# VisualightMicroBulb_04.net
KiCad netlist of a schematic drawn in EAGLE
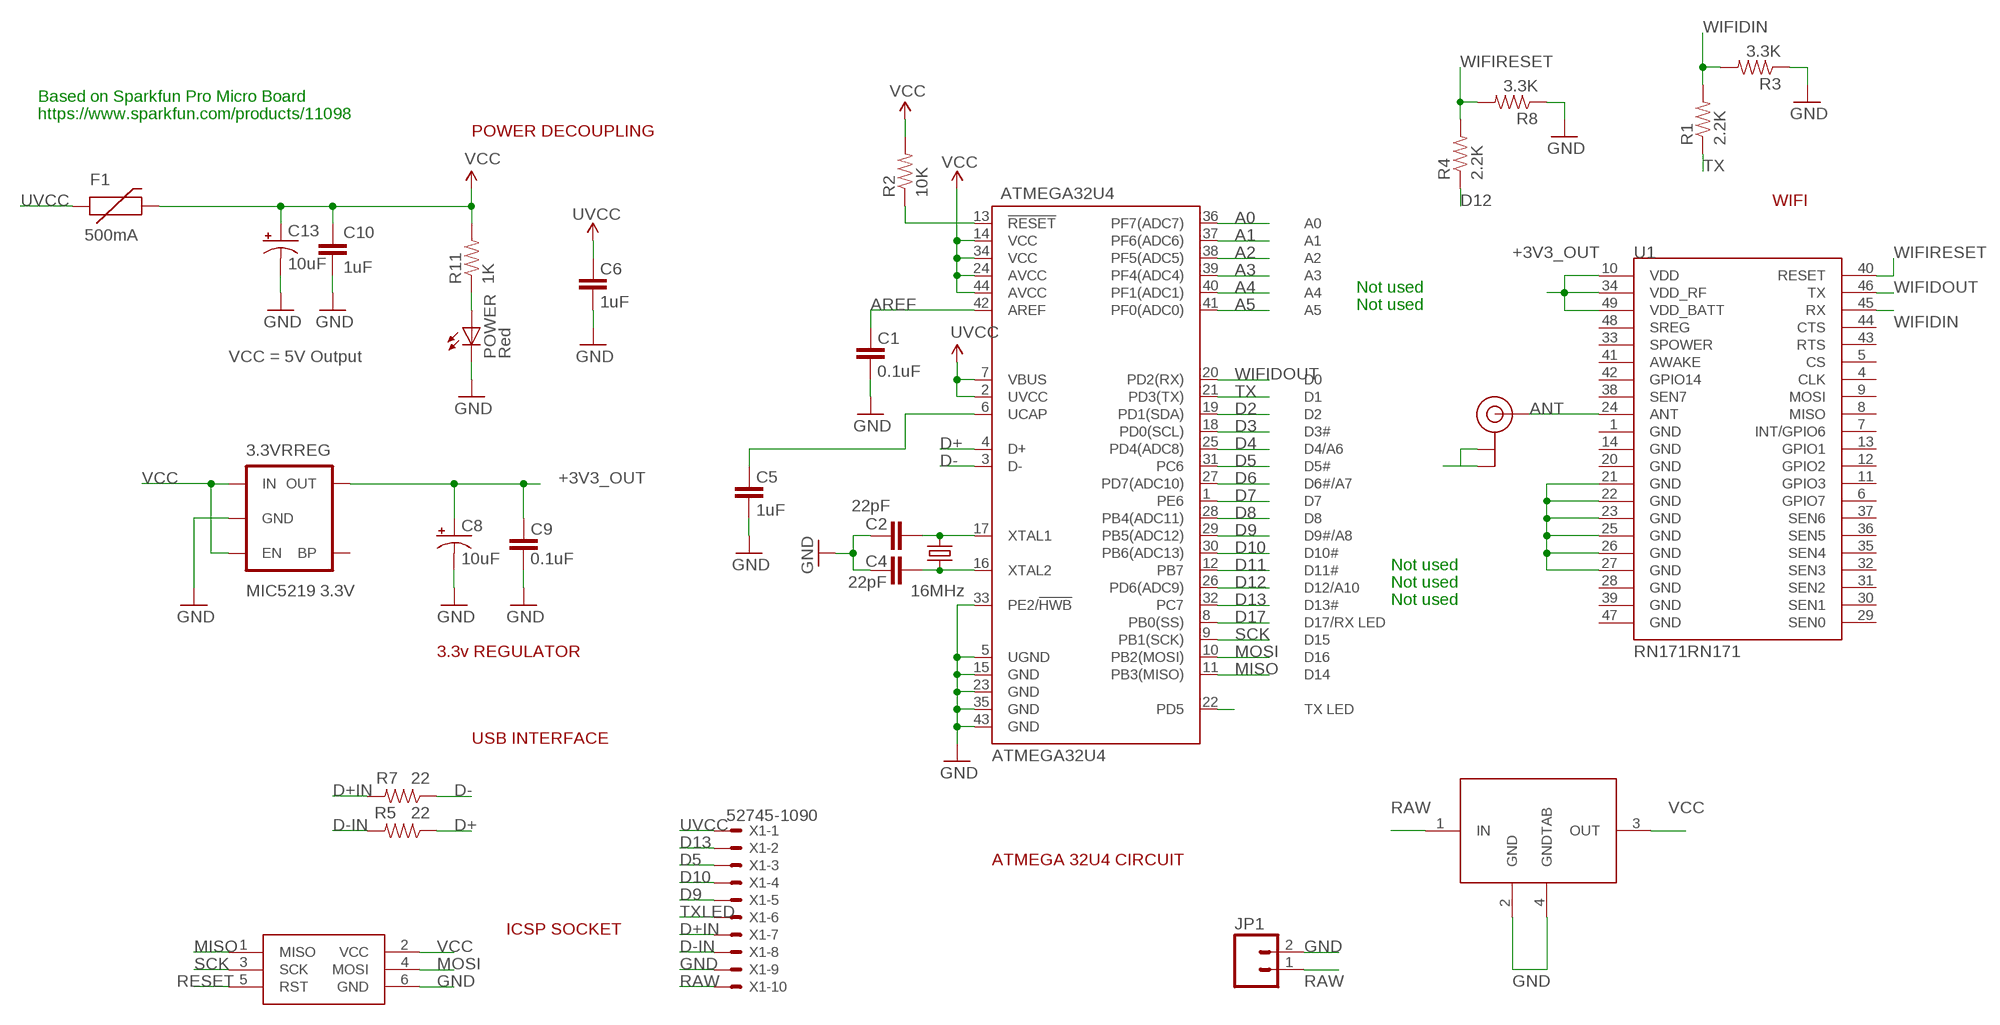
[diagram p0: schematic, sheet 1]

(export (version "E")
  (design (tool "Eeschema 10.0.6"))
  (components
    (comp (ref "3.3VRREG")
      (value "MIC5219 3.3V")
      (footprint "eagle-import:SOT23-5")
      (libsource (lib "eagle-import") (part "V_REG_MIC52193.3V"))
    )
    (comp (ref "ATMEGA32U4")
      (value "ATMEGA32U4")
      (footprint "eagle-import:SPARKFUN-DIGITALIC_TQFP44")
      (libsource (lib "eagle-import") (part "ATMEGA32U4TQFP"))
    )
    (comp (ref "C1")
      (value "0.1uF")
      (footprint "eagle-import:0402-CAP")
      (libsource (lib "eagle-import") (part "CAP0402-CAP"))
    )
    (comp (ref "C2")
      (value "22pF")
      (footprint "eagle-import:0402-CAP")
      (libsource (lib "eagle-import") (part "CAP0402-CAP"))
    )
    (comp (ref "C4")
      (value "22pF")
      (footprint "eagle-import:0402-CAP")
      (libsource (lib "eagle-import") (part "CAP0402-CAP"))
    )
    (comp (ref "C5")
      (value "1uF")
      (footprint "eagle-import:0402-CAP")
      (libsource (lib "eagle-import") (part "CAP0402-CAP"))
    )
    (comp (ref "C6")
      (value "1uF")
      (footprint "eagle-import:0402-CAP")
      (libsource (lib "eagle-import") (part "CAP0402-CAP"))
    )
    (comp (ref "C8")
      (value "10uF")
      (footprint "eagle-import:EIA3216")
      (libsource (lib "eagle-import") (part "CAP_POL1206"))
    )
    (comp (ref "C9")
      (value "0.1uF")
      (footprint "eagle-import:0402-CAP")
      (libsource (lib "eagle-import") (part "CAP0402-CAP"))
    )
    (comp (ref "C10")
      (value "1uF")
      (footprint "eagle-import:0402-CAP")
      (libsource (lib "eagle-import") (part "CAP0402-CAP"))
    )
    (comp (ref "C13")
      (value "10uF")
      (footprint "eagle-import:EIA3216")
      (libsource (lib "eagle-import") (part "CAP_POL1206"))
    )
    (comp (ref "F1")
      (value "500mA")
      (footprint "eagle-import:PTC-1206")
      (libsource (lib "eagle-import") (part "PTCSMD"))
    )
    (comp (ref "ISP1")
      (value "AVRISP-6")
      (footprint "eagle-import:AVRISP")
      (libsource (lib "eagle-import") (part "AVRISP-6"))
    )
    (comp (ref "JP1")
      (value "M02PTH")
      (footprint "eagle-import:1X02")
      (libsource (lib "eagle-import") (part "M02PTH"))
    )
    (comp (ref "POWER")
      (value "Red")
      (footprint "eagle-import:LED-0603")
      (libsource (lib "eagle-import") (part "LED0603"))
    )
    (comp (ref "R1")
      (value "2.2K")
      (footprint "eagle-import:0402-RES")
      (libsource (lib "eagle-import") (part "RESISTOR0402-RES"))
    )
    (comp (ref "R2")
      (value "10K")
      (footprint "eagle-import:0402-RES")
      (libsource (lib "eagle-import") (part "RESISTOR0402-RES"))
    )
    (comp (ref "R3")
      (value "3.3K")
      (footprint "eagle-import:0402-RES")
      (libsource (lib "eagle-import") (part "RESISTOR0402-RES"))
    )
    (comp (ref "R4")
      (value "2.2K")
      (footprint "eagle-import:0402-RES")
      (libsource (lib "eagle-import") (part "RESISTOR0402-RES"))
    )
    (comp (ref "R5")
      (value "22")
      (footprint "eagle-import:0402-RES")
      (libsource (lib "eagle-import") (part "RESISTOR0402-RES"))
    )
    (comp (ref "R7")
      (value "22")
      (footprint "eagle-import:0402-RES")
      (libsource (lib "eagle-import") (part "RESISTOR0402-RES"))
    )
    (comp (ref "R8")
      (value "3.3K")
      (footprint "eagle-import:0402-RES")
      (libsource (lib "eagle-import") (part "RESISTOR0402-RES"))
    )
    (comp (ref "R11")
      (value "1K")
      (footprint "eagle-import:0402-RES")
      (libsource (lib "eagle-import") (part "RESISTOR0402-RES"))
    )
    (comp (ref "U$1")
      (value "U.FL")
      (footprint "eagle-import:U.FL")
      (libsource (lib "eagle-import") (part "U.FL"))
    )
    (comp (ref "U$2")
      (value "MIC5239")
      (footprint "eagle-import:SOT223")
      (libsource (lib "eagle-import") (part "MIC5239"))
    )
    (comp (ref "U1")
      (value "RN171RN171")
      (footprint "eagle-import:RN171")
      (libsource (lib "eagle-import") (part "RN171RN171"))
    )
    (comp (ref "X1")
      (value "52745-1090")
      (footprint "eagle-import:52745-1090")
      (libsource (lib "eagle-import") (part "52745-1090"))
    )
    (comp (ref "Y1")
      (value "16MHz")
      (footprint "eagle-import:CRYSTAL-SMD-5X3")
      (libsource (lib "eagle-import") (part "CRYSTAL5X3"))
    )
  )
  (nets
    (net (code "1") (name "/+3V3_OUT") (class "Default")
      (node (ref "3.3VRREG") (pin "5") (pinfunction "OUT_5") (pintype "passive"))
      (node (ref "C8") (pin "A") (pinfunction "+_A") (pintype "passive"))
      (node (ref "C9") (pin "2") (pinfunction "2_2") (pintype "passive"))
      (node (ref "U1") (pin "10") (pinfunction "VDD_10") (pintype "bidirectional"))
      (node (ref "U1") (pin "34") (pinfunction "VDD_RF_34") (pintype "bidirectional"))
      (node (ref "U1") (pin "49") (pinfunction "VDD_BATT_49") (pintype "bidirectional"))
    )
    (net (code "2") (name "/A0") (class "Default")
      (node (ref "ATMEGA32U4") (pin "36") (pinfunction "PF7(ADC7)_36") (pintype "bidirectional"))
    )
    (net (code "3") (name "/A1") (class "Default")
      (node (ref "ATMEGA32U4") (pin "37") (pinfunction "PF6(ADC6)_37") (pintype "bidirectional"))
    )
    (net (code "4") (name "/A2") (class "Default")
      (node (ref "ATMEGA32U4") (pin "38") (pinfunction "PF5(ADC5)_38") (pintype "bidirectional"))
    )
    (net (code "5") (name "/A3") (class "Default")
      (node (ref "ATMEGA32U4") (pin "39") (pinfunction "PF4(ADC4)_39") (pintype "bidirectional"))
    )
    (net (code "6") (name "/A4") (class "Default")
      (node (ref "ATMEGA32U4") (pin "40") (pinfunction "PF1(ADC1)_40") (pintype "bidirectional"))
    )
    (net (code "7") (name "/A5") (class "Default")
      (node (ref "ATMEGA32U4") (pin "41") (pinfunction "PF0(ADC0)_41") (pintype "bidirectional"))
    )
    (net (code "8") (name "/ANT") (class "Default")
      (node (ref "U$1") (pin "P$3") (pinfunction "SIGNAL_P$3") (pintype "bidirectional"))
      (node (ref "U1") (pin "24") (pinfunction "ANT_24") (pintype "bidirectional"))
    )
    (net (code "9") (name "/AREF") (class "Default")
      (node (ref "ATMEGA32U4") (pin "42") (pinfunction "AREF_42") (pintype "bidirectional"))
      (node (ref "C1") (pin "2") (pinfunction "2_2") (pintype "passive"))
    )
    (net (code "10") (name "/D+") (class "Default")
      (node (ref "ATMEGA32U4") (pin "4") (pinfunction "D+_4") (pintype "bidirectional"))
      (node (ref "R5") (pin "1") (pinfunction "1_1") (pintype "passive"))
    )
    (net (code "11") (name "/D+IN") (class "Default")
      (node (ref "R7") (pin "2") (pinfunction "2_2") (pintype "passive"))
      (node (ref "X1") (pin "7") (pinfunction "S_7") (pintype "passive"))
    )
    (net (code "12") (name "/D-") (class "Default")
      (node (ref "ATMEGA32U4") (pin "3") (pinfunction "D-_3") (pintype "bidirectional"))
      (node (ref "R7") (pin "1") (pinfunction "1_1") (pintype "passive"))
    )
    (net (code "13") (name "/D-IN") (class "Default")
      (node (ref "R5") (pin "2") (pinfunction "2_2") (pintype "passive"))
      (node (ref "X1") (pin "8") (pinfunction "S_8") (pintype "passive"))
    )
    (net (code "14") (name "/D2") (class "Default")
      (node (ref "ATMEGA32U4") (pin "19") (pinfunction "PD1(SDA)_19") (pintype "bidirectional"))
    )
    (net (code "15") (name "/D3") (class "Default")
      (node (ref "ATMEGA32U4") (pin "18") (pinfunction "PD0(SCL)_18") (pintype "bidirectional"))
    )
    (net (code "16") (name "/D4") (class "Default")
      (node (ref "ATMEGA32U4") (pin "25") (pinfunction "PD4(ADC8)_25") (pintype "bidirectional"))
    )
    (net (code "17") (name "/D5") (class "Default")
      (node (ref "ATMEGA32U4") (pin "31") (pinfunction "PC6_31") (pintype "bidirectional"))
      (node (ref "X1") (pin "3") (pinfunction "S_3") (pintype "passive"))
    )
    (net (code "18") (name "/D6") (class "Default")
      (node (ref "ATMEGA32U4") (pin "27") (pinfunction "PD7(ADC10)_27") (pintype "bidirectional"))
    )
    (net (code "19") (name "/D7") (class "Default")
      (node (ref "ATMEGA32U4") (pin "1") (pinfunction "PE6_1") (pintype "bidirectional"))
    )
    (net (code "20") (name "/D8") (class "Default")
      (node (ref "ATMEGA32U4") (pin "28") (pinfunction "PB4(ADC11)_28") (pintype "bidirectional"))
    )
    (net (code "21") (name "/D9") (class "Default")
      (node (ref "ATMEGA32U4") (pin "29") (pinfunction "PB5(ADC12)_29") (pintype "bidirectional"))
      (node (ref "X1") (pin "5") (pinfunction "S_5") (pintype "passive"))
    )
    (net (code "22") (name "/D10") (class "Default")
      (node (ref "ATMEGA32U4") (pin "30") (pinfunction "PB6(ADC13)_30") (pintype "bidirectional"))
      (node (ref "X1") (pin "4") (pinfunction "S_4") (pintype "passive"))
    )
    (net (code "23") (name "/D11") (class "Default")
      (node (ref "ATMEGA32U4") (pin "12") (pinfunction "PB7_12") (pintype "bidirectional"))
    )
    (net (code "24") (name "/D12") (class "Default")
      (node (ref "ATMEGA32U4") (pin "26") (pinfunction "PD6(ADC9)_26") (pintype "bidirectional"))
      (node (ref "R4") (pin "1") (pinfunction "1_1") (pintype "passive"))
    )
    (net (code "25") (name "/D13") (class "Default")
      (node (ref "ATMEGA32U4") (pin "32") (pinfunction "PC7_32") (pintype "bidirectional"))
      (node (ref "X1") (pin "2") (pinfunction "S_2") (pintype "passive"))
    )
    (net (code "26") (name "/D17") (class "Default")
      (node (ref "ATMEGA32U4") (pin "8") (pinfunction "PB0(SS)_8") (pintype "bidirectional"))
    )
    (net (code "27") (name "/MISO") (class "Default")
      (node (ref "ATMEGA32U4") (pin "11") (pinfunction "PB3(MISO)_11") (pintype "bidirectional"))
      (node (ref "ISP1") (pin "1") (pinfunction "MISO_1") (pintype "input"))
    )
    (net (code "28") (name "/MOSI") (class "Default")
      (node (ref "ATMEGA32U4") (pin "10") (pinfunction "PB2(MOSI)_10") (pintype "bidirectional"))
      (node (ref "ISP1") (pin "4") (pinfunction "MOSI_4") (pintype "output"))
    )
    (net (code "29") (name "/RAW") (class "Default")
      (node (ref "JP1") (pin "1") (pinfunction "1_1") (pintype "passive"))
      (node (ref "U$2") (pin "1") (pinfunction "IN_1") (pintype "input"))
      (node (ref "X1") (pin "10") (pinfunction "S_10") (pintype "passive"))
    )
    (net (code "30") (name "/RESET") (class "Default")
      (node (ref "ATMEGA32U4") (pin "13") (pinfunction "~{RESET}_13") (pintype "bidirectional"))
      (node (ref "ISP1") (pin "5") (pinfunction "RST_5") (pintype "output"))
      (node (ref "R2") (pin "1") (pinfunction "1_1") (pintype "passive"))
    )
    (net (code "31") (name "/SCK") (class "Default")
      (node (ref "ATMEGA32U4") (pin "9") (pinfunction "PB1(SCK)_9") (pintype "bidirectional"))
      (node (ref "ISP1") (pin "3") (pinfunction "SCK_3") (pintype "output"))
    )
    (net (code "32") (name "/TX") (class "Default")
      (node (ref "ATMEGA32U4") (pin "21") (pinfunction "PD3(TX)_21") (pintype "bidirectional"))
      (node (ref "R1") (pin "1") (pinfunction "1_1") (pintype "passive"))
    )
    (net (code "33") (name "/TXLED") (class "Default")
      (node (ref "ATMEGA32U4") (pin "22") (pinfunction "PD5_22") (pintype "bidirectional"))
      (node (ref "X1") (pin "6") (pinfunction "S_6") (pintype "passive"))
    )
    (net (code "34") (name "/WIFIDIN") (class "Default")
      (node (ref "R1") (pin "2") (pinfunction "2_2") (pintype "passive"))
      (node (ref "R3") (pin "2") (pinfunction "2_2") (pintype "passive"))
      (node (ref "U1") (pin "45") (pinfunction "RX_45") (pintype "bidirectional"))
    )
    (net (code "35") (name "/WIFIDOUT") (class "Default")
      (node (ref "ATMEGA32U4") (pin "20") (pinfunction "PD2(RX)_20") (pintype "bidirectional"))
      (node (ref "U1") (pin "46") (pinfunction "TX_46") (pintype "bidirectional"))
    )
    (net (code "36") (name "/WIFIRESET") (class "Default")
      (node (ref "R4") (pin "2") (pinfunction "2_2") (pintype "passive"))
      (node (ref "R8") (pin "2") (pinfunction "2_2") (pintype "passive"))
      (node (ref "U1") (pin "40") (pinfunction "RESET_40") (pintype "bidirectional"))
    )
    (net (code "37") (name "GND") (class "Default")
      (node (ref "3.3VRREG") (pin "2") (pinfunction "GND_2") (pintype "input"))
      (node (ref "ATMEGA32U4") (pin "15") (pinfunction "GND_15") (pintype "bidirectional"))
      (node (ref "ATMEGA32U4") (pin "23") (pinfunction "GND_23") (pintype "bidirectional"))
      (node (ref "ATMEGA32U4") (pin "33") (pinfunction "PE2/~{HWB}_33") (pintype "bidirectional"))
      (node (ref "ATMEGA32U4") (pin "35") (pinfunction "GND_35") (pintype "bidirectional"))
      (node (ref "ATMEGA32U4") (pin "43") (pinfunction "GND_43") (pintype "bidirectional"))
      (node (ref "ATMEGA32U4") (pin "5") (pinfunction "UGND_5") (pintype "bidirectional"))
      (node (ref "C1") (pin "1") (pinfunction "1_1") (pintype "passive"))
      (node (ref "C10") (pin "2") (pinfunction "2_2") (pintype "passive"))
      (node (ref "C13") (pin "C") (pinfunction "-_C") (pintype "passive"))
      (node (ref "C2") (pin "2") (pinfunction "2_2") (pintype "passive"))
      (node (ref "C4") (pin "2") (pinfunction "2_2") (pintype "passive"))
      (node (ref "C5") (pin "1") (pinfunction "1_1") (pintype "passive"))
      (node (ref "C6") (pin "1") (pinfunction "1_1") (pintype "passive"))
      (node (ref "C8") (pin "C") (pinfunction "-_C") (pintype "passive"))
      (node (ref "C9") (pin "1") (pinfunction "1_1") (pintype "passive"))
      (node (ref "ISP1") (pin "6") (pinfunction "GND_6") (pintype "power_in"))
      (node (ref "JP1") (pin "2") (pinfunction "2_2") (pintype "passive"))
      (node (ref "POWER") (pin "C") (pinfunction "C_C") (pintype "passive"))
      (node (ref "R3") (pin "1") (pinfunction "1_1") (pintype "passive"))
      (node (ref "R8") (pin "1") (pinfunction "1_1") (pintype "passive"))
      (node (ref "U$1") (pin "P$1") (pinfunction "GND_P$1") (pintype "bidirectional"))
      (node (ref "U$1") (pin "P$2") (pinfunction "GND_P$2") (pintype "bidirectional"))
      (node (ref "U$2") (pin "2") (pinfunction "GND_2") (pintype "power_in"))
      (node (ref "U$2") (pin "4") (pinfunction "GNDTAB_4") (pintype "power_in"))
      (node (ref "U1") (pin "21") (pinfunction "GND_21") (pintype "bidirectional"))
      (node (ref "U1") (pin "22") (pinfunction "GND_22") (pintype "bidirectional"))
      (node (ref "U1") (pin "23") (pinfunction "GND_23") (pintype "bidirectional"))
      (node (ref "U1") (pin "25") (pinfunction "GND_25") (pintype "bidirectional"))
      (node (ref "U1") (pin "26") (pinfunction "GND_26") (pintype "bidirectional"))
      (node (ref "U1") (pin "27") (pinfunction "GND_27") (pintype "bidirectional"))
      (node (ref "X1") (pin "9") (pinfunction "S_9") (pintype "passive"))
    )
    (net (code "38") (name "Net-(ATMEGA32U4-UCAP)") (class "Default")
      (node (ref "ATMEGA32U4") (pin "6") (pinfunction "UCAP_6") (pintype "bidirectional"))
      (node (ref "C5") (pin "2") (pinfunction "2_2") (pintype "passive"))
    )
    (net (code "39") (name "Net-(ATMEGA32U4-XTAL1)") (class "Default")
      (node (ref "ATMEGA32U4") (pin "17") (pinfunction "XTAL1_17") (pintype "bidirectional"))
      (node (ref "C2") (pin "1") (pinfunction "1_1") (pintype "passive"))
      (node (ref "Y1") (pin "3") (pinfunction "2_3") (pintype "passive"))
    )
    (net (code "40") (name "Net-(ATMEGA32U4-XTAL2)") (class "Default")
      (node (ref "ATMEGA32U4") (pin "16") (pinfunction "XTAL2_16") (pintype "bidirectional"))
      (node (ref "C4") (pin "1") (pinfunction "1_1") (pintype "passive"))
      (node (ref "Y1") (pin "1") (pinfunction "1_1") (pintype "passive"))
    )
    (net (code "41") (name "Net-(POWER-PadA)") (class "Default")
      (node (ref "POWER") (pin "A") (pinfunction "A_A") (pintype "passive"))
      (node (ref "R11") (pin "1") (pinfunction "1_1") (pintype "passive"))
    )
    (net (code "42") (name "UVCC") (class "Default")
      (node (ref "ATMEGA32U4") (pin "2") (pinfunction "UVCC_2") (pintype "bidirectional"))
      (node (ref "ATMEGA32U4") (pin "7") (pinfunction "VBUS_7") (pintype "bidirectional"))
      (node (ref "C6") (pin "2") (pinfunction "2_2") (pintype "passive"))
      (node (ref "F1") (pin "1") (pinfunction "1_1") (pintype "bidirectional"))
      (node (ref "X1") (pin "1") (pinfunction "S_1") (pintype "passive"))
    )
    (net (code "43") (name "VCC") (class "Default")
      (node (ref "3.3VRREG") (pin "1") (pinfunction "IN_1") (pintype "input"))
      (node (ref "3.3VRREG") (pin "3") (pinfunction "EN_3") (pintype "input"))
      (node (ref "ATMEGA32U4") (pin "14") (pinfunction "VCC_14") (pintype "bidirectional"))
      (node (ref "ATMEGA32U4") (pin "24") (pinfunction "AVCC_24") (pintype "bidirectional"))
      (node (ref "ATMEGA32U4") (pin "34") (pinfunction "VCC_34") (pintype "bidirectional"))
      (node (ref "ATMEGA32U4") (pin "44") (pinfunction "AVCC_44") (pintype "bidirectional"))
      (node (ref "C10") (pin "1") (pinfunction "1_1") (pintype "passive"))
      (node (ref "C13") (pin "A") (pinfunction "+_A") (pintype "passive"))
      (node (ref "F1") (pin "2") (pinfunction "2_2") (pintype "bidirectional"))
      (node (ref "ISP1") (pin "2") (pinfunction "VCC_2") (pintype "power_in"))
      (node (ref "R11") (pin "2") (pinfunction "2_2") (pintype "passive"))
      (node (ref "R2") (pin "2") (pinfunction "2_2") (pintype "passive"))
      (node (ref "U$2") (pin "3") (pinfunction "OUT_3") (pintype "output"))
    )
    (net (code "44") (name "unconnected-(3.3VRREG-BP-Pad4)") (class "Default")
      (node (ref "3.3VRREG") (pin "4") (pinfunction "BP_4") (pintype "input"))
    )
    (net (code "45") (name "unconnected-(U1-AWAKE-Pad41)") (class "Default")
      (node (ref "U1") (pin "41") (pinfunction "AWAKE_41") (pintype "bidirectional"))
    )
    (net (code "46") (name "unconnected-(U1-CLK-Pad4)") (class "Default")
      (node (ref "U1") (pin "4") (pinfunction "CLK_4") (pintype "bidirectional"))
    )
    (net (code "47") (name "unconnected-(U1-CS-Pad5)") (class "Default")
      (node (ref "U1") (pin "5") (pinfunction "CS_5") (pintype "bidirectional"))
    )
    (net (code "48") (name "unconnected-(U1-CTS-Pad44)") (class "Default")
      (node (ref "U1") (pin "44") (pinfunction "CTS_44") (pintype "bidirectional"))
    )
    (net (code "49") (name "unconnected-(U1-GND-Pad1)") (class "Default")
      (node (ref "U1") (pin "1") (pinfunction "GND_1") (pintype "bidirectional"))
    )
    (net (code "50") (name "unconnected-(U1-GND-Pad14)") (class "Default")
      (node (ref "U1") (pin "14") (pinfunction "GND_14") (pintype "bidirectional"))
    )
    (net (code "51") (name "unconnected-(U1-GND-Pad20)") (class "Default")
      (node (ref "U1") (pin "20") (pinfunction "GND_20") (pintype "bidirectional"))
    )
    (net (code "52") (name "unconnected-(U1-GND-Pad28)") (class "Default")
      (node (ref "U1") (pin "28") (pinfunction "GND_28") (pintype "bidirectional"))
    )
    (net (code "53") (name "unconnected-(U1-GND-Pad39)") (class "Default")
      (node (ref "U1") (pin "39") (pinfunction "GND_39") (pintype "bidirectional"))
    )
    (net (code "54") (name "unconnected-(U1-GND-Pad47)") (class "Default")
      (node (ref "U1") (pin "47") (pinfunction "GND_47") (pintype "bidirectional"))
    )
    (net (code "55") (name "unconnected-(U1-GPIO1-Pad13)") (class "Default")
      (node (ref "U1") (pin "13") (pinfunction "GPIO1_13") (pintype "bidirectional"))
    )
    (net (code "56") (name "unconnected-(U1-GPIO2-Pad12)") (class "Default")
      (node (ref "U1") (pin "12") (pinfunction "GPIO2_12") (pintype "bidirectional"))
    )
    (net (code "57") (name "unconnected-(U1-GPIO3-Pad11)") (class "Default")
      (node (ref "U1") (pin "11") (pinfunction "GPIO3_11") (pintype "bidirectional"))
    )
    (net (code "58") (name "unconnected-(U1-GPIO7-Pad6)") (class "Default")
      (node (ref "U1") (pin "6") (pinfunction "GPIO7_6") (pintype "bidirectional"))
    )
    (net (code "59") (name "unconnected-(U1-GPIO14-Pad42)") (class "Default")
      (node (ref "U1") (pin "42") (pinfunction "GPIO14_42") (pintype "bidirectional"))
    )
    (net (code "60") (name "unconnected-(U1-INT{slash}GPIO6-Pad7)") (class "Default")
      (node (ref "U1") (pin "7") (pinfunction "INT/GPIO6_7") (pintype "bidirectional"))
    )
    (net (code "61") (name "unconnected-(U1-MISO-Pad8)") (class "Default")
      (node (ref "U1") (pin "8") (pinfunction "MISO_8") (pintype "bidirectional"))
    )
    (net (code "62") (name "unconnected-(U1-MOSI-Pad9)") (class "Default")
      (node (ref "U1") (pin "9") (pinfunction "MOSI_9") (pintype "bidirectional"))
    )
    (net (code "63") (name "unconnected-(U1-RTS-Pad43)") (class "Default")
      (node (ref "U1") (pin "43") (pinfunction "RTS_43") (pintype "bidirectional"))
    )
    (net (code "64") (name "unconnected-(U1-SEN0-Pad29)") (class "Default")
      (node (ref "U1") (pin "29") (pinfunction "SEN0_29") (pintype "bidirectional"))
    )
    (net (code "65") (name "unconnected-(U1-SEN1-Pad30)") (class "Default")
      (node (ref "U1") (pin "30") (pinfunction "SEN1_30") (pintype "bidirectional"))
    )
    (net (code "66") (name "unconnected-(U1-SEN2-Pad31)") (class "Default")
      (node (ref "U1") (pin "31") (pinfunction "SEN2_31") (pintype "bidirectional"))
    )
    (net (code "67") (name "unconnected-(U1-SEN3-Pad32)") (class "Default")
      (node (ref "U1") (pin "32") (pinfunction "SEN3_32") (pintype "bidirectional"))
    )
    (net (code "68") (name "unconnected-(U1-SEN4-Pad35)") (class "Default")
      (node (ref "U1") (pin "35") (pinfunction "SEN4_35") (pintype "bidirectional"))
    )
    (net (code "69") (name "unconnected-(U1-SEN5-Pad36)") (class "Default")
      (node (ref "U1") (pin "36") (pinfunction "SEN5_36") (pintype "bidirectional"))
    )
    (net (code "70") (name "unconnected-(U1-SEN6-Pad37)") (class "Default")
      (node (ref "U1") (pin "37") (pinfunction "SEN6_37") (pintype "bidirectional"))
    )
    (net (code "71") (name "unconnected-(U1-SEN7-Pad38)") (class "Default")
      (node (ref "U1") (pin "38") (pinfunction "SEN7_38") (pintype "bidirectional"))
    )
    (net (code "72") (name "unconnected-(U1-SPOWER-Pad33)") (class "Default")
      (node (ref "U1") (pin "33") (pinfunction "SPOWER_33") (pintype "bidirectional"))
    )
    (net (code "73") (name "unconnected-(U1-SREG-Pad48)") (class "Default")
      (node (ref "U1") (pin "48") (pinfunction "SREG_48") (pintype "bidirectional"))
    )
  )
)
